# Mainboard_Encoder_Connector.net
KiCad netlist of a schematic drawn in Altium Designer
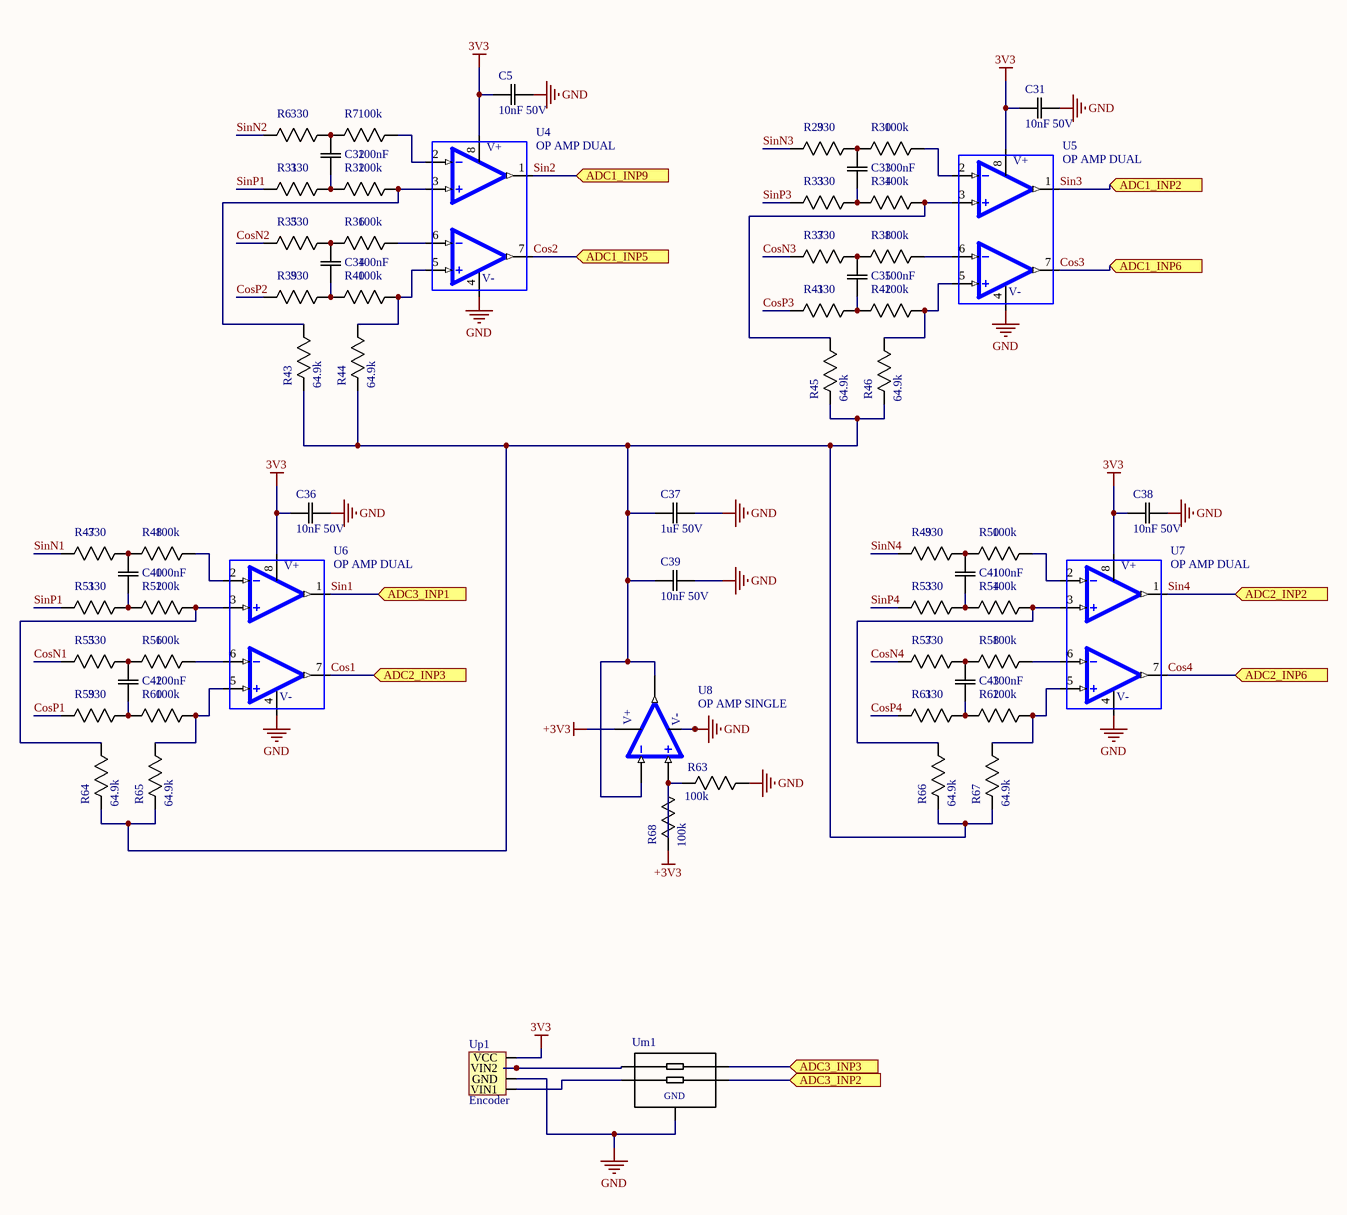
[diagram p0: Mainboard_Encoder Connector.SchDoc]

(export (version "E")
  (design (tool "Eeschema 10.0.6"))
  (components
    (comp (ref "C5")
      (value "10nF 50V")
      (footprint "0805")
      (description "CAP CER 10000PF 50V X7R 0805")
      (fields (field (name "TOLERANCE") "10%"))
      (libsource (lib "AltiumLibraries") (part "CAP 10nF 50V"))
    )
    (comp (ref "C31")
      (value "10nF 50V")
      (footprint "0805")
      (description "CAP CER 10000PF 50V X7R 0805")
      (fields (field (name "TOLERANCE") "10%"))
      (libsource (lib "AltiumLibraries") (part "CAP 10nF 50V"))
    )
    (comp (ref "C32") (value "100nF") (libsource (lib "AltiumLibraries") (part "CAPACITOR_SCH")))
    (comp (ref "C33") (value "100nF") (libsource (lib "AltiumLibraries") (part "CAPACITOR_SCH")))
    (comp (ref "C34") (value "100nF") (libsource (lib "AltiumLibraries") (part "CAPACITOR_SCH")))
    (comp (ref "C35") (value "100nF") (libsource (lib "AltiumLibraries") (part "CAPACITOR_SCH")))
    (comp (ref "C36")
      (value "10nF 50V")
      (footprint "0805")
      (description "CAP CER 10000PF 50V X7R 0805")
      (fields (field (name "TOLERANCE") "10%"))
      (libsource (lib "AltiumLibraries") (part "CAP 10nF 50V"))
    )
    (comp (ref "C37")
      (value "1uF 50V")
      (footprint "0805")
      (description "CAP CER 1UF 50V X7R 0805")
      (fields (field (name "TOLERANCE") "10%"))
      (libsource (lib "AltiumLibraries") (part "CAP 1uF 50V"))
    )
    (comp (ref "C38")
      (value "10nF 50V")
      (footprint "0805")
      (description "CAP CER 10000PF 50V X7R 0805")
      (fields (field (name "TOLERANCE") "10%"))
      (libsource (lib "AltiumLibraries") (part "CAP 10nF 50V"))
    )
    (comp (ref "C39")
      (value "10nF 50V")
      (footprint "0805")
      (description "CAP CER 10000PF 50V X7R 0805")
      (fields (field (name "TOLERANCE") "10%"))
      (libsource (lib "AltiumLibraries") (part "CAP 10nF 50V"))
    )
    (comp (ref "C40") (value "100nF") (libsource (lib "AltiumLibraries") (part "CAPACITOR_SCH")))
    (comp (ref "C41") (value "100nF") (libsource (lib "AltiumLibraries") (part "CAPACITOR_SCH")))
    (comp (ref "C42") (value "100nF") (libsource (lib "AltiumLibraries") (part "CAPACITOR_SCH")))
    (comp (ref "C43") (value "100nF") (libsource (lib "AltiumLibraries") (part "CAPACITOR_SCH")))
    (comp (ref "R6")
      (value "330")
      (footprint "0805")
      (description "RES SMD 330 OHM 1% 1/8W 0805")
      (fields (field (name "TOLERANCE") "1%"))
      (libsource (lib "") (part "RES 330.0 1/8W - 1%_1"))
    )
    (comp (ref "R7")
      (value "100k")
      (footprint "0805")
      (description "RES SMD 100K OHM 1% 1/8W 0805")
      (fields (field (name "TOLERANCE") "1%"))
      (libsource (lib "AltiumLibraries") (part "RES 100k 1/8W - 1%"))
    )
    (comp (ref "R29")
      (value "330")
      (footprint "0805")
      (description "RES SMD 330 OHM 1% 1/8W 0805")
      (fields (field (name "TOLERANCE") "1%"))
      (libsource (lib "") (part "RES 330.0 1/8W - 1%_1"))
    )
    (comp (ref "R30")
      (value "100k")
      (footprint "0805")
      (description "RES SMD 100K OHM 1% 1/8W 0805")
      (fields (field (name "TOLERANCE") "1%"))
      (libsource (lib "AltiumLibraries") (part "RES 100k 1/8W - 1%"))
    )
    (comp (ref "R31")
      (value "330")
      (footprint "0805")
      (description "RES SMD 330 OHM 1% 1/8W 0805")
      (fields (field (name "TOLERANCE") "1%"))
      (libsource (lib "AltiumLibraries") (part "RES 330.0 1/8W - 1%"))
    )
    (comp (ref "R32")
      (value "100k")
      (footprint "0805")
      (description "RES SMD 100K OHM 1% 1/8W 0805")
      (fields (field (name "TOLERANCE") "1%"))
      (libsource (lib "") (part "RES 100k 1/8W - 1%_1"))
    )
    (comp (ref "R33")
      (value "330")
      (footprint "0805")
      (description "RES SMD 330 OHM 1% 1/8W 0805")
      (fields (field (name "TOLERANCE") "1%"))
      (libsource (lib "AltiumLibraries") (part "RES 330.0 1/8W - 1%"))
    )
    (comp (ref "R34")
      (value "100k")
      (footprint "0805")
      (description "RES SMD 100K OHM 1% 1/8W 0805")
      (fields (field (name "TOLERANCE") "1%"))
      (libsource (lib "") (part "RES 100k 1/8W - 1%_1"))
    )
    (comp (ref "R35")
      (value "330")
      (footprint "0805")
      (description "RES SMD 330 OHM 1% 1/8W 0805")
      (fields (field (name "TOLERANCE") "1%"))
      (libsource (lib "") (part "RES 330.0 1/8W - 1%_1"))
    )
    (comp (ref "R36")
      (value "100k")
      (footprint "0805")
      (description "RES SMD 100K OHM 1% 1/8W 0805")
      (fields (field (name "TOLERANCE") "1%"))
      (libsource (lib "AltiumLibraries") (part "RES 100k 1/8W - 1%"))
    )
    (comp (ref "R37")
      (value "330")
      (footprint "0805")
      (description "RES SMD 330 OHM 1% 1/8W 0805")
      (fields (field (name "TOLERANCE") "1%"))
      (libsource (lib "") (part "RES 330.0 1/8W - 1%_1"))
    )
    (comp (ref "R38")
      (value "100k")
      (footprint "0805")
      (description "RES SMD 100K OHM 1% 1/8W 0805")
      (fields (field (name "TOLERANCE") "1%"))
      (libsource (lib "AltiumLibraries") (part "RES 100k 1/8W - 1%"))
    )
    (comp (ref "R39")
      (value "330")
      (footprint "0805")
      (description "RES SMD 330 OHM 1% 1/8W 0805")
      (fields (field (name "TOLERANCE") "1%"))
      (libsource (lib "AltiumLibraries") (part "RES 330.0 1/8W - 1%"))
    )
    (comp (ref "R40")
      (value "100k")
      (footprint "0805")
      (description "RES SMD 100K OHM 1% 1/8W 0805")
      (fields (field (name "TOLERANCE") "1%"))
      (libsource (lib "") (part "RES 100k 1/8W - 1%_1"))
    )
    (comp (ref "R41")
      (value "330")
      (footprint "0805")
      (description "RES SMD 330 OHM 1% 1/8W 0805")
      (fields (field (name "TOLERANCE") "1%"))
      (libsource (lib "AltiumLibraries") (part "RES 330.0 1/8W - 1%"))
    )
    (comp (ref "R42")
      (value "100k")
      (footprint "0805")
      (description "RES SMD 100K OHM 1% 1/8W 0805")
      (fields (field (name "TOLERANCE") "1%"))
      (libsource (lib "") (part "RES 100k 1/8W - 1%_1"))
    )
    (comp (ref "R43")
      (value "64.9k")
      (footprint "0805")
      (description "RES SMD 64.9K OHM 1% 1/8W 0805")
      (fields (field (name "TOLERANCE") "1%"))
      (libsource (lib "AltiumLibraries") (part "RES 64.9k 1/8W"))
    )
    (comp (ref "R44")
      (value "64.9k")
      (footprint "0805")
      (description "RES SMD 64.9K OHM 1% 1/8W 0805")
      (fields (field (name "TOLERANCE") "1%"))
      (libsource (lib "AltiumLibraries") (part "RES 64.9k 1/8W"))
    )
    (comp (ref "R45")
      (value "64.9k")
      (footprint "0805")
      (description "RES SMD 64.9K OHM 1% 1/8W 0805")
      (fields (field (name "TOLERANCE") "1%"))
      (libsource (lib "AltiumLibraries") (part "RES 64.9k 1/8W"))
    )
    (comp (ref "R46")
      (value "64.9k")
      (footprint "0805")
      (description "RES SMD 64.9K OHM 1% 1/8W 0805")
      (fields (field (name "TOLERANCE") "1%"))
      (libsource (lib "AltiumLibraries") (part "RES 64.9k 1/8W"))
    )
    (comp (ref "R47")
      (value "330")
      (footprint "0805")
      (description "RES SMD 330 OHM 1% 1/8W 0805")
      (fields (field (name "TOLERANCE") "1%"))
      (libsource (lib "") (part "RES 330.0 1/8W - 1%_1"))
    )
    (comp (ref "R48")
      (value "100k")
      (footprint "0805")
      (description "RES SMD 100K OHM 1% 1/8W 0805")
      (fields (field (name "TOLERANCE") "1%"))
      (libsource (lib "AltiumLibraries") (part "RES 100k 1/8W - 1%"))
    )
    (comp (ref "R49")
      (value "330")
      (footprint "0805")
      (description "RES SMD 330 OHM 1% 1/8W 0805")
      (fields (field (name "TOLERANCE") "1%"))
      (libsource (lib "") (part "RES 330.0 1/8W - 1%_1"))
    )
    (comp (ref "R50")
      (value "100k")
      (footprint "0805")
      (description "RES SMD 100K OHM 1% 1/8W 0805")
      (fields (field (name "TOLERANCE") "1%"))
      (libsource (lib "AltiumLibraries") (part "RES 100k 1/8W - 1%"))
    )
    (comp (ref "R51")
      (value "330")
      (footprint "0805")
      (description "RES SMD 330 OHM 1% 1/8W 0805")
      (fields (field (name "TOLERANCE") "1%"))
      (libsource (lib "AltiumLibraries") (part "RES 330.0 1/8W - 1%"))
    )
    (comp (ref "R52")
      (value "100k")
      (footprint "0805")
      (description "RES SMD 100K OHM 1% 1/8W 0805")
      (fields (field (name "TOLERANCE") "1%"))
      (libsource (lib "") (part "RES 100k 1/8W - 1%_1"))
    )
    (comp (ref "R53")
      (value "330")
      (footprint "0805")
      (description "RES SMD 330 OHM 1% 1/8W 0805")
      (fields (field (name "TOLERANCE") "1%"))
      (libsource (lib "AltiumLibraries") (part "RES 330.0 1/8W - 1%"))
    )
    (comp (ref "R54")
      (value "100k")
      (footprint "0805")
      (description "RES SMD 100K OHM 1% 1/8W 0805")
      (fields (field (name "TOLERANCE") "1%"))
      (libsource (lib "") (part "RES 100k 1/8W - 1%_1"))
    )
    (comp (ref "R55")
      (value "330")
      (footprint "0805")
      (description "RES SMD 330 OHM 1% 1/8W 0805")
      (fields (field (name "TOLERANCE") "1%"))
      (libsource (lib "") (part "RES 330.0 1/8W - 1%_1"))
    )
    (comp (ref "R56")
      (value "100k")
      (footprint "0805")
      (description "RES SMD 100K OHM 1% 1/8W 0805")
      (fields (field (name "TOLERANCE") "1%"))
      (libsource (lib "AltiumLibraries") (part "RES 100k 1/8W - 1%"))
    )
    (comp (ref "R57")
      (value "330")
      (footprint "0805")
      (description "RES SMD 330 OHM 1% 1/8W 0805")
      (fields (field (name "TOLERANCE") "1%"))
      (libsource (lib "") (part "RES 330.0 1/8W - 1%_1"))
    )
    (comp (ref "R58")
      (value "100k")
      (footprint "0805")
      (description "RES SMD 100K OHM 1% 1/8W 0805")
      (fields (field (name "TOLERANCE") "1%"))
      (libsource (lib "AltiumLibraries") (part "RES 100k 1/8W - 1%"))
    )
    (comp (ref "R59")
      (value "330")
      (footprint "0805")
      (description "RES SMD 330 OHM 1% 1/8W 0805")
      (fields (field (name "TOLERANCE") "1%"))
      (libsource (lib "AltiumLibraries") (part "RES 330.0 1/8W - 1%"))
    )
    (comp (ref "R60")
      (value "100k")
      (footprint "0805")
      (description "RES SMD 100K OHM 1% 1/8W 0805")
      (fields (field (name "TOLERANCE") "1%"))
      (libsource (lib "") (part "RES 100k 1/8W - 1%_1"))
    )
    (comp (ref "R61")
      (value "330")
      (footprint "0805")
      (description "RES SMD 330 OHM 1% 1/8W 0805")
      (fields (field (name "TOLERANCE") "1%"))
      (libsource (lib "AltiumLibraries") (part "RES 330.0 1/8W - 1%"))
    )
    (comp (ref "R62")
      (value "100k")
      (footprint "0805")
      (description "RES SMD 100K OHM 1% 1/8W 0805")
      (fields (field (name "TOLERANCE") "1%"))
      (libsource (lib "") (part "RES 100k 1/8W - 1%_1"))
    )
    (comp (ref "R63")
      (value "100k")
      (footprint "0805")
      (description "RES SMD 100K OHM 1% 1/8W 0805")
      (fields (field (name "TOLERANCE") "1%"))
      (libsource (lib "") (part "RES 100k 1/8W - 1%_1"))
    )
    (comp (ref "R64")
      (value "64.9k")
      (footprint "0805")
      (description "RES SMD 64.9K OHM 1% 1/8W 0805")
      (fields (field (name "TOLERANCE") "1%"))
      (libsource (lib "AltiumLibraries") (part "RES 64.9k 1/8W"))
    )
    (comp (ref "R65")
      (value "64.9k")
      (footprint "0805")
      (description "RES SMD 64.9K OHM 1% 1/8W 0805")
      (fields (field (name "TOLERANCE") "1%"))
      (libsource (lib "AltiumLibraries") (part "RES 64.9k 1/8W"))
    )
    (comp (ref "R66")
      (value "64.9k")
      (footprint "0805")
      (description "RES SMD 64.9K OHM 1% 1/8W 0805")
      (fields (field (name "TOLERANCE") "1%"))
      (libsource (lib "AltiumLibraries") (part "RES 64.9k 1/8W"))
    )
    (comp (ref "R67")
      (value "64.9k")
      (footprint "0805")
      (description "RES SMD 64.9K OHM 1% 1/8W 0805")
      (fields (field (name "TOLERANCE") "1%"))
      (libsource (lib "AltiumLibraries") (part "RES 64.9k 1/8W"))
    )
    (comp (ref "R68")
      (value "100k")
      (footprint "0805")
      (description "RES SMD 100K OHM 1% 1/8W 0805")
      (fields (field (name "TOLERANCE") "1%"))
      (libsource (lib "") (part "RES 100k 1/8W - 1%_1"))
    )
    (comp (ref "U4")
      (value "OP AMP DUAL")
      (footprint "8-MSOP")
      (description "IC OPAMP VFB 50KHZ RRO 8MSOP")
      (fields
        (field (name "MANUFACTURER") "Analog Devices")
        (field (name "MANUFACTURER PART NUMBER") "ADA4505-2ARMZ")
      )
      (libsource (lib "AltiumLibraries") (part "OP AMP DUAL"))
    )
    (comp (ref "U5")
      (value "OP AMP DUAL")
      (footprint "8-MSOP")
      (description "IC OPAMP VFB 50KHZ RRO 8MSOP")
      (fields
        (field (name "MANUFACTURER") "Analog Devices")
        (field (name "MANUFACTURER PART NUMBER") "ADA4505-2ARMZ")
      )
      (libsource (lib "AltiumLibraries") (part "OP AMP DUAL"))
    )
    (comp (ref "U6")
      (value "OP AMP DUAL")
      (footprint "8-MSOP")
      (description "IC OPAMP VFB 50KHZ RRO 8MSOP")
      (fields
        (field (name "MANUFACTURER") "Analog Devices")
        (field (name "MANUFACTURER PART NUMBER") "ADA4505-2ARMZ")
      )
      (libsource (lib "AltiumLibraries") (part "OP AMP DUAL"))
    )
    (comp (ref "U7")
      (value "OP AMP DUAL")
      (footprint "8-MSOP")
      (description "IC OPAMP VFB 50KHZ RRO 8MSOP")
      (fields
        (field (name "MANUFACTURER") "Analog Devices")
        (field (name "MANUFACTURER PART NUMBER") "ADA4505-2ARMZ")
      )
      (libsource (lib "AltiumLibraries") (part "OP AMP DUAL"))
    )
    (comp (ref "U8")
      (value "OP AMP SINGLE")
      (footprint "SOT95P280X145-5N")
      (description "ANALOG DEVICES - ADA4505-1ARJZ-R7 - IC, AMPLIF. OPER., R-R, CMOS, SOT23-5")
      (fields
        (field (name "MANUFACTURER") "Analog Devices")
        (field (name "MANUFACTURER PART NUMBER") "ADA4505-1ARJZ-R7")
      )
      (libsource (lib "AltiumLibraries") (part "OP AMP SINGLE"))
    )
    (comp (ref "Um1")
      (value "EMI")
      (footprint "SOT-665")
      (description "RC (Pi) EMI Filter 2nd Order Low Pass 2 Channel R = 100Ohms, C = 19pF (Total)  SOT-665")
      (fields (field (name "MF") "Nexperia USA Inc.") (field (name "MP") "IP4256CZ5-W,115"))
      (libsource (lib "AltiumLibraries") (part "IP4256CZ5-W"))
    )
    (comp (ref "Up1")
      (value "Encoder")
      (footprint "EncoderConnector")
      (description "CONN HEADER R/A 4POS 1.5MM")
      (fields (field (name "MF") "JST Sales America Inc.") (field (name "MP") "S4B-ZR(LF)(SN)"))
      (libsource (lib "AltiumLibraries") (part "Encoder Connector"))
    )
  )
  (nets
    (net (code "1") (name "+3V3") (class "Default")
      (node (ref "R68") (pin "2") (pinfunction "R2_2") (pintype "passive"))
      (node (ref "U8") (pin "5") (pinfunction "V+_5") (pintype "power_in"))
    )
    (net (code "2") (name "/ADC3_INP2") (class "Default")
      (node (ref "Um1") (pin "4") (pinfunction "P$4_4") (pintype "passive"))
    )
    (net (code "3") (name "/ADC3_INP3") (class "Default")
      (node (ref "Um1") (pin "5") (pinfunction "P$5_5") (pintype "passive"))
    )
    (net (code "4") (name "/Cos1") (class "Default")
      (node (ref "U6") (pin "7") (pinfunction "OUTB_7") (pintype "output"))
    )
    (net (code "5") (name "/Cos2") (class "Default")
      (node (ref "U4") (pin "7") (pinfunction "OUTB_7") (pintype "output"))
    )
    (net (code "6") (name "/Cos3") (class "Default")
      (node (ref "U5") (pin "7") (pinfunction "OUTB_7") (pintype "output"))
    )
    (net (code "7") (name "/Cos4") (class "Default")
      (node (ref "U7") (pin "7") (pinfunction "OUTB_7") (pintype "output"))
    )
    (net (code "8") (name "/CosN1") (class "Default")
      (node (ref "R55") (pin "2") (pinfunction "R2_2") (pintype "passive"))
    )
    (net (code "9") (name "/CosN2") (class "Default")
      (node (ref "R35") (pin "2") (pinfunction "R2_2") (pintype "passive"))
    )
    (net (code "10") (name "/CosN3") (class "Default")
      (node (ref "R37") (pin "2") (pinfunction "R2_2") (pintype "passive"))
    )
    (net (code "11") (name "/CosN4") (class "Default")
      (node (ref "R57") (pin "2") (pinfunction "R2_2") (pintype "passive"))
    )
    (net (code "12") (name "/CosP1") (class "Default")
      (node (ref "R59") (pin "2") (pinfunction "R2_2") (pintype "passive"))
    )
    (net (code "13") (name "/CosP2") (class "Default")
      (node (ref "R39") (pin "2") (pinfunction "R2_2") (pintype "passive"))
    )
    (net (code "14") (name "/CosP3") (class "Default")
      (node (ref "R41") (pin "2") (pinfunction "R2_2") (pintype "passive"))
    )
    (net (code "15") (name "/CosP4") (class "Default")
      (node (ref "R61") (pin "2") (pinfunction "R2_2") (pintype "passive"))
    )
    (net (code "16") (name "/Sin1") (class "Default")
      (node (ref "U6") (pin "1") (pinfunction "OUTA_1") (pintype "output"))
    )
    (net (code "17") (name "/Sin2") (class "Default")
      (node (ref "U4") (pin "1") (pinfunction "OUTA_1") (pintype "output"))
    )
    (net (code "18") (name "/Sin3") (class "Default")
      (node (ref "U5") (pin "1") (pinfunction "OUTA_1") (pintype "output"))
    )
    (net (code "19") (name "/Sin4") (class "Default")
      (node (ref "U7") (pin "1") (pinfunction "OUTA_1") (pintype "output"))
    )
    (net (code "20") (name "/SinN1") (class "Default")
      (node (ref "R47") (pin "2") (pinfunction "R2_2") (pintype "passive"))
    )
    (net (code "21") (name "/SinN2") (class "Default")
      (node (ref "R6") (pin "2") (pinfunction "R2_2") (pintype "passive"))
    )
    (net (code "22") (name "/SinN3") (class "Default")
      (node (ref "R29") (pin "2") (pinfunction "R2_2") (pintype "passive"))
    )
    (net (code "23") (name "/SinN4") (class "Default")
      (node (ref "R49") (pin "2") (pinfunction "R2_2") (pintype "passive"))
    )
    (net (code "24") (name "/SinP1") (class "Default")
      (node (ref "R31") (pin "2") (pinfunction "R2_2") (pintype "passive"))
      (node (ref "R51") (pin "2") (pinfunction "R2_2") (pintype "passive"))
    )
    (net (code "25") (name "/SinP3") (class "Default")
      (node (ref "R33") (pin "2") (pinfunction "R2_2") (pintype "passive"))
    )
    (net (code "26") (name "/SinP4") (class "Default")
      (node (ref "R53") (pin "2") (pinfunction "R2_2") (pintype "passive"))
    )
    (net (code "27") (name "3V3") (class "Default")
      (node (ref "C31") (pin "1") (pinfunction "C1_1") (pintype "passive"))
      (node (ref "C36") (pin "1") (pinfunction "C1_1") (pintype "passive"))
      (node (ref "C38") (pin "1") (pinfunction "C1_1") (pintype "passive"))
      (node (ref "C5") (pin "1") (pinfunction "C1_1") (pintype "passive"))
      (node (ref "U4") (pin "8") (pinfunction "V+_8") (pintype "power_in"))
      (node (ref "U5") (pin "8") (pinfunction "V+_8") (pintype "power_in"))
      (node (ref "U6") (pin "8") (pinfunction "V+_8") (pintype "power_in"))
      (node (ref "U7") (pin "8") (pinfunction "V+_8") (pintype "power_in"))
      (node (ref "Up1") (pin "VCC") (pinfunction "VCC_VCC") (pintype "power_in"))
    )
    (net (code "28") (name "GND") (class "Default")
      (node (ref "C31") (pin "2") (pinfunction "C2_2") (pintype "passive"))
      (node (ref "C36") (pin "2") (pinfunction "C2_2") (pintype "passive"))
      (node (ref "C37") (pin "2") (pinfunction "C2_2") (pintype "passive"))
      (node (ref "C38") (pin "2") (pinfunction "C2_2") (pintype "passive"))
      (node (ref "C39") (pin "2") (pinfunction "C2_2") (pintype "passive"))
      (node (ref "C5") (pin "2") (pinfunction "C2_2") (pintype "passive"))
      (node (ref "R63") (pin "1") (pinfunction "R1_1") (pintype "passive"))
      (node (ref "U4") (pin "4") (pinfunction "V-_4") (pintype "power_in"))
      (node (ref "U5") (pin "4") (pinfunction "V-_4") (pintype "power_in"))
      (node (ref "U6") (pin "4") (pinfunction "V-_4") (pintype "power_in"))
      (node (ref "U7") (pin "4") (pinfunction "V-_4") (pintype "power_in"))
      (node (ref "U8") (pin "2") (pinfunction "V-_2") (pintype "power_in"))
      (node (ref "Um1") (pin "2") (pinfunction "P$2_2") (pintype "passive"))
      (node (ref "Up1") (pin "GND") (pinfunction "GND_GND") (pintype "power_in"))
    )
    (net (code "29") (name "Net-(C32-C1)") (class "Default")
      (node (ref "C32") (pin "1") (pinfunction "C1_1") (pintype "passive"))
      (node (ref "R31") (pin "1") (pinfunction "R1_1") (pintype "passive"))
      (node (ref "R32") (pin "2") (pinfunction "R2_2") (pintype "passive"))
    )
    (net (code "30") (name "Net-(C32-C2)") (class "Default")
      (node (ref "C32") (pin "2") (pinfunction "C2_2") (pintype "passive"))
      (node (ref "R6") (pin "1") (pinfunction "R1_1") (pintype "passive"))
      (node (ref "R7") (pin "2") (pinfunction "R2_2") (pintype "passive"))
    )
    (net (code "31") (name "Net-(C33-C1)") (class "Default")
      (node (ref "C33") (pin "1") (pinfunction "C1_1") (pintype "passive"))
      (node (ref "R33") (pin "1") (pinfunction "R1_1") (pintype "passive"))
      (node (ref "R34") (pin "2") (pinfunction "R2_2") (pintype "passive"))
    )
    (net (code "32") (name "Net-(C33-C2)") (class "Default")
      (node (ref "C33") (pin "2") (pinfunction "C2_2") (pintype "passive"))
      (node (ref "R29") (pin "1") (pinfunction "R1_1") (pintype "passive"))
      (node (ref "R30") (pin "2") (pinfunction "R2_2") (pintype "passive"))
    )
    (net (code "33") (name "Net-(C34-C1)") (class "Default")
      (node (ref "C34") (pin "1") (pinfunction "C1_1") (pintype "passive"))
      (node (ref "R39") (pin "1") (pinfunction "R1_1") (pintype "passive"))
      (node (ref "R40") (pin "2") (pinfunction "R2_2") (pintype "passive"))
    )
    (net (code "34") (name "Net-(C34-C2)") (class "Default")
      (node (ref "C34") (pin "2") (pinfunction "C2_2") (pintype "passive"))
      (node (ref "R35") (pin "1") (pinfunction "R1_1") (pintype "passive"))
      (node (ref "R36") (pin "2") (pinfunction "R2_2") (pintype "passive"))
    )
    (net (code "35") (name "Net-(C35-C1)") (class "Default")
      (node (ref "C35") (pin "1") (pinfunction "C1_1") (pintype "passive"))
      (node (ref "R41") (pin "1") (pinfunction "R1_1") (pintype "passive"))
      (node (ref "R42") (pin "2") (pinfunction "R2_2") (pintype "passive"))
    )
    (net (code "36") (name "Net-(C35-C2)") (class "Default")
      (node (ref "C35") (pin "2") (pinfunction "C2_2") (pintype "passive"))
      (node (ref "R37") (pin "1") (pinfunction "R1_1") (pintype "passive"))
      (node (ref "R38") (pin "2") (pinfunction "R2_2") (pintype "passive"))
    )
    (net (code "37") (name "Net-(C37-C1)") (class "Default")
      (node (ref "C37") (pin "1") (pinfunction "C1_1") (pintype "passive"))
      (node (ref "C39") (pin "1") (pinfunction "C1_1") (pintype "passive"))
      (node (ref "R43") (pin "2") (pinfunction "R2_2") (pintype "passive"))
      (node (ref "R44") (pin "2") (pinfunction "R2_2") (pintype "passive"))
      (node (ref "R45") (pin "2") (pinfunction "R2_2") (pintype "passive"))
      (node (ref "R46") (pin "2") (pinfunction "R2_2") (pintype "passive"))
      (node (ref "R64") (pin "2") (pinfunction "R2_2") (pintype "passive"))
      (node (ref "R65") (pin "2") (pinfunction "R2_2") (pintype "passive"))
      (node (ref "R66") (pin "2") (pinfunction "R2_2") (pintype "passive"))
      (node (ref "R67") (pin "2") (pinfunction "R2_2") (pintype "passive"))
      (node (ref "U8") (pin "1") (pinfunction "OUT_1") (pintype "output"))
      (node (ref "U8") (pin "4") (pinfunction "IN-_4") (pintype "input"))
    )
    (net (code "38") (name "Net-(C40-C1)") (class "Default")
      (node (ref "C40") (pin "1") (pinfunction "C1_1") (pintype "passive"))
      (node (ref "R51") (pin "1") (pinfunction "R1_1") (pintype "passive"))
      (node (ref "R52") (pin "2") (pinfunction "R2_2") (pintype "passive"))
    )
    (net (code "39") (name "Net-(C40-C2)") (class "Default")
      (node (ref "C40") (pin "2") (pinfunction "C2_2") (pintype "passive"))
      (node (ref "R47") (pin "1") (pinfunction "R1_1") (pintype "passive"))
      (node (ref "R48") (pin "2") (pinfunction "R2_2") (pintype "passive"))
    )
    (net (code "40") (name "Net-(C41-C1)") (class "Default")
      (node (ref "C41") (pin "1") (pinfunction "C1_1") (pintype "passive"))
      (node (ref "R53") (pin "1") (pinfunction "R1_1") (pintype "passive"))
      (node (ref "R54") (pin "2") (pinfunction "R2_2") (pintype "passive"))
    )
    (net (code "41") (name "Net-(C41-C2)") (class "Default")
      (node (ref "C41") (pin "2") (pinfunction "C2_2") (pintype "passive"))
      (node (ref "R49") (pin "1") (pinfunction "R1_1") (pintype "passive"))
      (node (ref "R50") (pin "2") (pinfunction "R2_2") (pintype "passive"))
    )
    (net (code "42") (name "Net-(C42-C1)") (class "Default")
      (node (ref "C42") (pin "1") (pinfunction "C1_1") (pintype "passive"))
      (node (ref "R59") (pin "1") (pinfunction "R1_1") (pintype "passive"))
      (node (ref "R60") (pin "2") (pinfunction "R2_2") (pintype "passive"))
    )
    (net (code "43") (name "Net-(C42-C2)") (class "Default")
      (node (ref "C42") (pin "2") (pinfunction "C2_2") (pintype "passive"))
      (node (ref "R55") (pin "1") (pinfunction "R1_1") (pintype "passive"))
      (node (ref "R56") (pin "2") (pinfunction "R2_2") (pintype "passive"))
    )
    (net (code "44") (name "Net-(C43-C1)") (class "Default")
      (node (ref "C43") (pin "1") (pinfunction "C1_1") (pintype "passive"))
      (node (ref "R61") (pin "1") (pinfunction "R1_1") (pintype "passive"))
      (node (ref "R62") (pin "2") (pinfunction "R2_2") (pintype "passive"))
    )
    (net (code "45") (name "Net-(C43-C2)") (class "Default")
      (node (ref "C43") (pin "2") (pinfunction "C2_2") (pintype "passive"))
      (node (ref "R57") (pin "1") (pinfunction "R1_1") (pintype "passive"))
      (node (ref "R58") (pin "2") (pinfunction "R2_2") (pintype "passive"))
    )
    (net (code "46") (name "Net-(R7-R1)") (class "Default")
      (node (ref "R7") (pin "1") (pinfunction "R1_1") (pintype "passive"))
      (node (ref "U4") (pin "2") (pinfunction "INA-_2") (pintype "input"))
    )
    (net (code "47") (name "Net-(R30-R1)") (class "Default")
      (node (ref "R30") (pin "1") (pinfunction "R1_1") (pintype "passive"))
      (node (ref "U5") (pin "2") (pinfunction "INA-_2") (pintype "input"))
    )
    (net (code "48") (name "Net-(R32-R1)") (class "Default")
      (node (ref "R32") (pin "1") (pinfunction "R1_1") (pintype "passive"))
      (node (ref "R43") (pin "1") (pinfunction "R1_1") (pintype "passive"))
      (node (ref "U4") (pin "3") (pinfunction "INA+_3") (pintype "input"))
    )
    (net (code "49") (name "Net-(R34-R1)") (class "Default")
      (node (ref "R34") (pin "1") (pinfunction "R1_1") (pintype "passive"))
      (node (ref "R45") (pin "1") (pinfunction "R1_1") (pintype "passive"))
      (node (ref "U5") (pin "3") (pinfunction "INA+_3") (pintype "input"))
    )
    (net (code "50") (name "Net-(R36-R1)") (class "Default")
      (node (ref "R36") (pin "1") (pinfunction "R1_1") (pintype "passive"))
      (node (ref "U4") (pin "6") (pinfunction "INB-_6") (pintype "input"))
    )
    (net (code "51") (name "Net-(R38-R1)") (class "Default")
      (node (ref "R38") (pin "1") (pinfunction "R1_1") (pintype "passive"))
      (node (ref "U5") (pin "6") (pinfunction "INB-_6") (pintype "input"))
    )
    (net (code "52") (name "Net-(R40-R1)") (class "Default")
      (node (ref "R40") (pin "1") (pinfunction "R1_1") (pintype "passive"))
      (node (ref "R44") (pin "1") (pinfunction "R1_1") (pintype "passive"))
      (node (ref "U4") (pin "5") (pinfunction "INB+_5") (pintype "input"))
    )
    (net (code "53") (name "Net-(R42-R1)") (class "Default")
      (node (ref "R42") (pin "1") (pinfunction "R1_1") (pintype "passive"))
      (node (ref "R46") (pin "1") (pinfunction "R1_1") (pintype "passive"))
      (node (ref "U5") (pin "5") (pinfunction "INB+_5") (pintype "input"))
    )
    (net (code "54") (name "Net-(R48-R1)") (class "Default")
      (node (ref "R48") (pin "1") (pinfunction "R1_1") (pintype "passive"))
      (node (ref "U6") (pin "2") (pinfunction "INA-_2") (pintype "input"))
    )
    (net (code "55") (name "Net-(R50-R1)") (class "Default")
      (node (ref "R50") (pin "1") (pinfunction "R1_1") (pintype "passive"))
      (node (ref "U7") (pin "2") (pinfunction "INA-_2") (pintype "input"))
    )
    (net (code "56") (name "Net-(R52-R1)") (class "Default")
      (node (ref "R52") (pin "1") (pinfunction "R1_1") (pintype "passive"))
      (node (ref "R64") (pin "1") (pinfunction "R1_1") (pintype "passive"))
      (node (ref "U6") (pin "3") (pinfunction "INA+_3") (pintype "input"))
    )
    (net (code "57") (name "Net-(R54-R1)") (class "Default")
      (node (ref "R54") (pin "1") (pinfunction "R1_1") (pintype "passive"))
      (node (ref "R66") (pin "1") (pinfunction "R1_1") (pintype "passive"))
      (node (ref "U7") (pin "3") (pinfunction "INA+_3") (pintype "input"))
    )
    (net (code "58") (name "Net-(R56-R1)") (class "Default")
      (node (ref "R56") (pin "1") (pinfunction "R1_1") (pintype "passive"))
      (node (ref "U6") (pin "6") (pinfunction "INB-_6") (pintype "input"))
    )
    (net (code "59") (name "Net-(R58-R1)") (class "Default")
      (node (ref "R58") (pin "1") (pinfunction "R1_1") (pintype "passive"))
      (node (ref "U7") (pin "6") (pinfunction "INB-_6") (pintype "input"))
    )
    (net (code "60") (name "Net-(R60-R1)") (class "Default")
      (node (ref "R60") (pin "1") (pinfunction "R1_1") (pintype "passive"))
      (node (ref "R65") (pin "1") (pinfunction "R1_1") (pintype "passive"))
      (node (ref "U6") (pin "5") (pinfunction "INB+_5") (pintype "input"))
    )
    (net (code "61") (name "Net-(R62-R1)") (class "Default")
      (node (ref "R62") (pin "1") (pinfunction "R1_1") (pintype "passive"))
      (node (ref "R67") (pin "1") (pinfunction "R1_1") (pintype "passive"))
      (node (ref "U7") (pin "5") (pinfunction "INB+_5") (pintype "input"))
    )
    (net (code "62") (name "Net-(R63-R2)") (class "Default")
      (node (ref "R63") (pin "2") (pinfunction "R2_2") (pintype "passive"))
      (node (ref "R68") (pin "1") (pinfunction "R1_1") (pintype "passive"))
      (node (ref "U8") (pin "3") (pinfunction "IN+_3") (pintype "input"))
    )
    (net (code "63") (name "Net-(Um1-P$1)") (class "Default")
      (node (ref "Um1") (pin "1") (pinfunction "P$1_1") (pintype "passive"))
      (node (ref "Up1") (pin "VIN2") (pinfunction "VIN2_VIN2") (pintype "input"))
    )
    (net (code "64") (name "Net-(Um1-P$3)") (class "Default")
      (node (ref "Um1") (pin "3") (pinfunction "P$3_3") (pintype "passive"))
      (node (ref "Up1") (pin "VIN1") (pinfunction "VIN1_VIN1") (pintype "input"))
    )
  )
)
